# LAN9252-1.net
KiCad netlist of a schematic drawn in Altium Designer
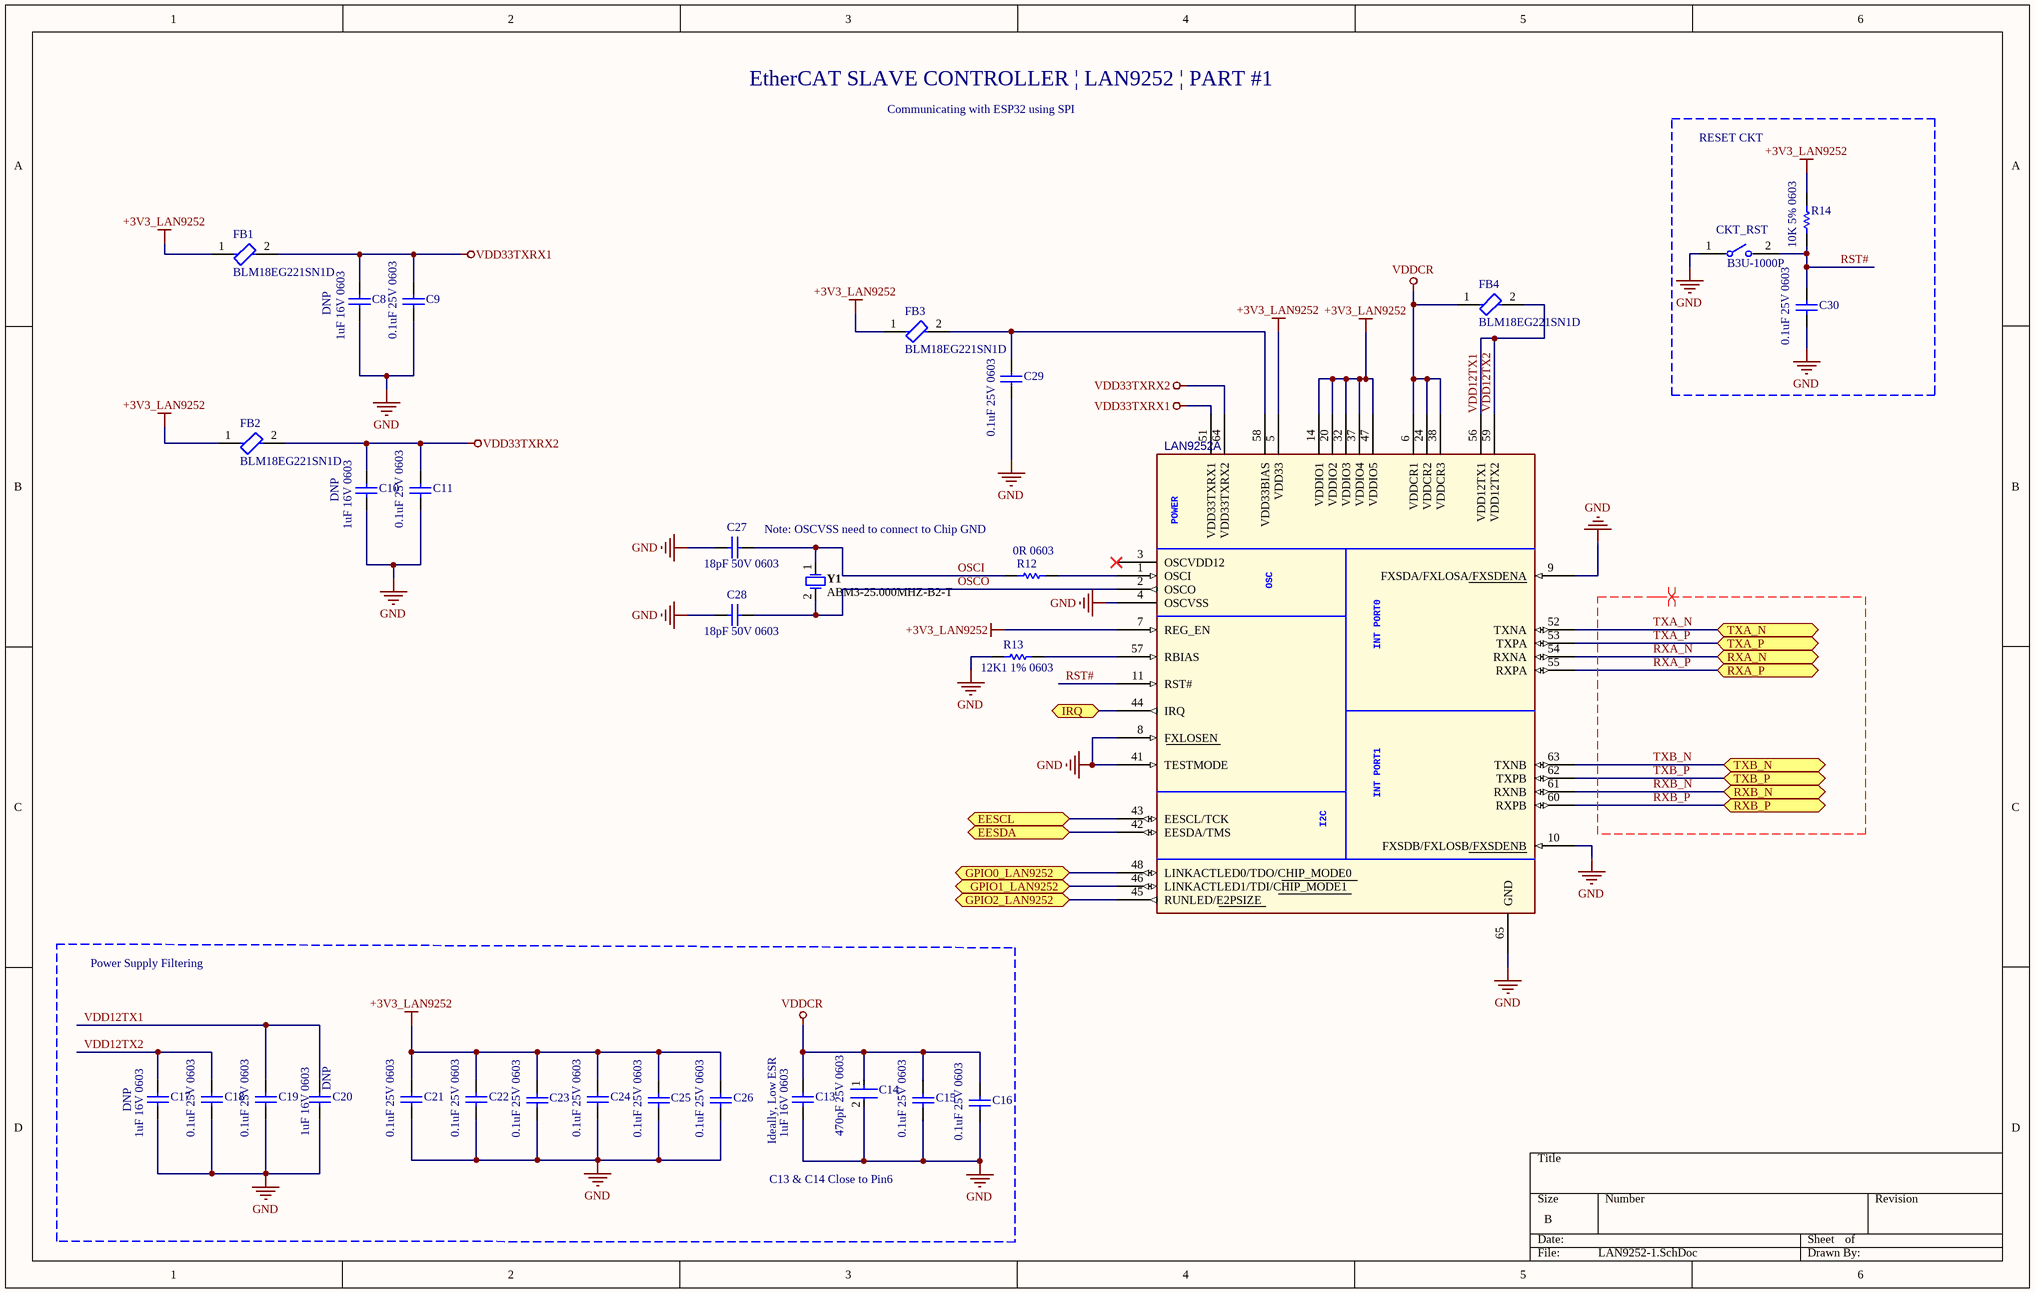
[diagram p0: LAN9252-1.SchDoc]

(export (version "E")
  (design (tool "Eeschema 10.0.6"))
  (components
    (comp (ref "C8")
      (value "1uF 16V 0603")
      (footprint "CAPC1608X90X35LL15T15")
      (fields (field (name "MANUFACTURER") "Kemet") (field (name "PART NUMBER") "C0603C105K4RACTU"))
      (libsource (lib "Altium Content Vault") (part "CAP"))
    )
    (comp (ref "C9")
      (value "0.1uF 25V 0603")
      (footprint "CAPC1608X90X35LL10T15")
      (fields (field (name "PART NUMBER") "GRM188R71E104KA01D") (field (name "MANUFACTURER") "Murata"))
      (libsource (lib "Altium Content Vault") (part "CAP"))
    )
    (comp (ref "C10")
      (value "1uF 16V 0603")
      (footprint "CAPC1608X90X35LL15T15")
      (fields (field (name "MANUFACTURER") "Kemet") (field (name "PART NUMBER") "C0603C105K4RACTU"))
      (libsource (lib "Altium Content Vault") (part "CAP"))
    )
    (comp (ref "C11")
      (value "0.1uF 25V 0603")
      (footprint "CAPC1608X90X35LL10T15")
      (fields (field (name "PART NUMBER") "GRM188R71E104KA01D") (field (name "MANUFACTURER") "Murata"))
      (libsource (lib "Altium Content Vault") (part "CAP"))
    )
    (comp (ref "C13")
      (value "1uF 16V 0603")
      (footprint "CAPC1608X90X35LL15T15")
      (fields (field (name "MANUFACTURER") "Kemet") (field (name "PART NUMBER") "C0603C105K4RACTU"))
      (libsource (lib "Altium Content Vault") (part "CAP"))
    )
    (comp (ref "C14")
      (value "470pF 25V 0603")
      (footprint "FP-C0603C-CF-MFG")
      (description "CAP CER 470PF 25V 10% X7R 0603")
      (fields (field (name "MANUFACTURER") "KEMET") (field (name "TOLERANCE") "0.1"))
      (libsource (lib "Altium Content Vault") (part "b4654b650e69147ec39a6b967a45e02"))
    )
    (comp (ref "C15")
      (value "0.1uF 25V 0603")
      (footprint "CAPC1608X90X35LL10T15")
      (fields (field (name "PART NUMBER") "GRM188R71E104KA01D") (field (name "MANUFACTURER") "Murata"))
      (libsource (lib "Altium Content Vault") (part "CAP"))
    )
    (comp (ref "C16")
      (value "0.1uF 25V 0603")
      (footprint "CAPC1608X90X35LL10T15")
      (fields (field (name "PART NUMBER") "GRM188R71E104KA01D") (field (name "MANUFACTURER") "Murata"))
      (libsource (lib "Altium Content Vault") (part "CAP"))
    )
    (comp (ref "C17")
      (value "1uF 16V 0603")
      (footprint "CAPC1608X90X35LL15T15")
      (fields (field (name "MANUFACTURER") "Kemet") (field (name "PART NUMBER") "C0603C105K4RACTU"))
      (libsource (lib "Altium Content Vault") (part "CAP"))
    )
    (comp (ref "C18")
      (value "0.1uF 25V 0603")
      (footprint "CAPC1608X90X35LL10T15")
      (fields (field (name "PART NUMBER") "GRM188R71E104KA01D") (field (name "MANUFACTURER") "Murata"))
      (libsource (lib "Altium Content Vault") (part "CAP"))
    )
    (comp (ref "C19")
      (value "0.1uF 25V 0603")
      (footprint "CAPC1608X90X35LL10T15")
      (fields (field (name "PART NUMBER") "GRM188R71E104KA01D") (field (name "MANUFACTURER") "Murata"))
      (libsource (lib "Altium Content Vault") (part "CAP"))
    )
    (comp (ref "C20")
      (value "1uF 16V 0603")
      (footprint "CAPC1608X90X35LL15T15")
      (fields (field (name "MANUFACTURER") "Kemet") (field (name "PART NUMBER") "C0603C105K4RACTU"))
      (libsource (lib "Altium Content Vault") (part "CAP"))
    )
    (comp (ref "C21")
      (value "0.1uF 25V 0603")
      (footprint "CAPC1608X90X35LL10T15")
      (fields (field (name "PART NUMBER") "GRM188R71E104KA01D") (field (name "MANUFACTURER") "Murata"))
      (libsource (lib "Altium Content Vault") (part "CAP"))
    )
    (comp (ref "C22")
      (value "0.1uF 25V 0603")
      (footprint "CAPC1608X90X35LL10T15")
      (fields (field (name "PART NUMBER") "GRM188R71E104KA01D") (field (name "MANUFACTURER") "Murata"))
      (libsource (lib "Altium Content Vault") (part "CAP"))
    )
    (comp (ref "C23")
      (value "0.1uF 25V 0603")
      (footprint "CAPC1608X90X35LL10T15")
      (fields (field (name "PART NUMBER") "GRM188R71E104KA01D") (field (name "MANUFACTURER") "Murata"))
      (libsource (lib "Altium Content Vault") (part "CAP"))
    )
    (comp (ref "C24")
      (value "0.1uF 25V 0603")
      (footprint "CAPC1608X90X35LL10T15")
      (fields (field (name "PART NUMBER") "GRM188R71E104KA01D") (field (name "MANUFACTURER") "Murata"))
      (libsource (lib "Altium Content Vault") (part "CAP"))
    )
    (comp (ref "C25")
      (value "0.1uF 25V 0603")
      (footprint "CAPC1608X90X35LL10T15")
      (fields (field (name "PART NUMBER") "GRM188R71E104KA01D") (field (name "MANUFACTURER") "Murata"))
      (libsource (lib "Altium Content Vault") (part "CAP"))
    )
    (comp (ref "C26")
      (value "0.1uF 25V 0603")
      (footprint "CAPC1608X90X35LL10T15")
      (fields (field (name "PART NUMBER") "GRM188R71E104KA01D") (field (name "MANUFACTURER") "Murata"))
      (libsource (lib "Altium Content Vault") (part "CAP"))
    )
    (comp (ref "C27")
      (value "18pF 50V 0603")
      (footprint "CAPC1608X90X40LL10T20")
      (description "Chip Capacitor, 18 pF, +/- 5%, 50 V, -55 to 125 degC, 0603 (1608 Metric), RoHS, Tape and Reel")
      (fields (field (name "TOLERANCE") "1%"))
      (libsource (lib "Altium Content Vault") (part "CAP-NP-2"))
    )
    (comp (ref "C28")
      (value "18pF 50V 0603")
      (footprint "CAPC1608X90X40LL10T20")
      (description "Chip Capacitor, 18 pF, +/- 5%, 50 V, -55 to 125 degC, 0603 (1608 Metric), RoHS, Tape and Reel")
      (fields (field (name "TOLERANCE") "1%"))
      (libsource (lib "Altium Content Vault") (part "CAP-NP-2"))
    )
    (comp (ref "C29")
      (value "0.1uF 25V 0603")
      (footprint "CAPC1608X90X35LL10T15")
      (fields (field (name "PART NUMBER") "GRM188R71E104KA01D") (field (name "MANUFACTURER") "Murata"))
      (libsource (lib "Altium Content Vault") (part "CAP"))
    )
    (comp (ref "C30")
      (value "0.1uF 25V 0603")
      (footprint "CAPC1608X90X35LL10T15")
      (fields (field (name "PART NUMBER") "GRM188R71E104KA01D") (field (name "MANUFACTURER") "Murata"))
      (libsource (lib "Altium Content Vault") (part "CAP"))
    )
    (comp (ref "CKT_RST")
      (value "B3U-1000P")
      (footprint "FP-B3U-1000P-MFG")
      (description "SWITCH TACTILE SPST-NO 0.05A 12V")
      (libsource (lib "Altium Content Vault") (part "ae622034201233ca1abcedc05908f33"))
    )
    (comp (ref "FB1")
      (value "BLM18EG221SN1D")
      (footprint "FP-BLM18-0_15-t0_8-MFG")
      (description "Chip Ferrite Bead, 0603, 220Ω @ 100MHz, 0.05Ω, 25%, 2A")
      (fields (field (name "TOLERANCE") "25%"))
      (libsource (lib "Altium Content Vault") (part "5f30dd21d616792df468990f7003faa"))
    )
    (comp (ref "FB2")
      (value "BLM18EG221SN1D")
      (footprint "FP-BLM18-0_15-t0_8-MFG")
      (description "Chip Ferrite Bead, 0603, 220Ω @ 100MHz, 0.05Ω, 25%, 2A")
      (fields (field (name "TOLERANCE") "25%"))
      (libsource (lib "Altium Content Vault") (part "5f30dd21d616792df468990f7003faa"))
    )
    (comp (ref "FB3")
      (value "BLM18EG221SN1D")
      (footprint "FP-BLM18-0_15-t0_8-MFG")
      (description "Chip Ferrite Bead, 0603, 220Ω @ 100MHz, 0.05Ω, 25%, 2A")
      (fields (field (name "TOLERANCE") "25%"))
      (libsource (lib "Altium Content Vault") (part "5f30dd21d616792df468990f7003faa"))
    )
    (comp (ref "FB4")
      (value "BLM18EG221SN1D")
      (footprint "FP-BLM18-0_15-t0_8-MFG")
      (description "Chip Ferrite Bead, 0603, 220Ω @ 100MHz, 0.05Ω, 25%, 2A")
      (fields (field (name "TOLERANCE") "25%"))
      (libsource (lib "Altium Content Vault") (part "5f30dd21d616792df468990f7003faa"))
    )
    (comp (ref "LAN9252")
      (value "~")
      (footprint "LAN9252_QFN")
      (description "IC, 2/3-Port EtherCAT® Slave Controller, QFN64")
      (fields (field (name "OWNER") "Manikandan"))
      (libsource (lib "UNG_UNG") (part "LAN9252_QFN64"))
    )
    (comp (ref "R12")
      (value "0R 0603")
      (footprint "RESC1608X55X25ML10T15")
      (description "Chip Resistor, 0 Ohm, +/- 5%, 0.1 W, -55 to 155 degC, 0603 (1608 Metric), RoHS, Tape and Reel")
      (fields (field (name "TOLERANCE") "5%") (field (name "MANUFACTURER") "Yageo"))
      (libsource (lib "Altium Content Vault") (part "RES-2"))
    )
    (comp (ref "R13")
      (value "12K1 1% 0603")
      (footprint "RESC0603X28X15ML05T05")
      (fields (field (name "PART NUMBER") "CRCW020112K1FNED") (field (name "MANUFACTURER") "Vishay Dale"))
      (libsource (lib "Altium Content Vault") (part "RES"))
    )
    (comp (ref "R14")
      (value "10K 5% 0603")
      (footprint "RESC1608X55X25ML10T15")
      (description "Chip Resistor, 10 KOhm, +/- 1%, 01 W, -55 to 155 degC, 0603 (1608 Metric), RoHS, Tape and Reel")
      (fields (field (name "MANUFACTURER") "Yageo") (field (name "TOLERANCE") "1%"))
      (libsource (lib "Altium Content Vault") (part "RES-2"))
    )
    (comp (ref "Y1")
      (value "ABM3-25.000MHZ-B2-T")
      (footprint "ABRA-ABM3_V")
      (description "Miniature Ceramic Crystal, 25 MHz, +/- 20 ppm, -20 to 70 degC, 2-Pin SMD, RoHS, Tape and Reel")
      (fields (field (name "TOLERANCE") "20PPM") (field (name "MANUFACTURER") "ABRACON"))
      (libsource (lib "Altium Content Vault") (part "XTAL-1-2-2"))
    )
  )
  (nets
    (net (code "1") (name "+3V3_LAN9252") (class "Default")
      (node (ref "C21") (pin "2") (pinfunction "2_2") (pintype "passive"))
      (node (ref "C22") (pin "2") (pinfunction "2_2") (pintype "passive"))
      (node (ref "C23") (pin "2") (pinfunction "2_2") (pintype "passive"))
      (node (ref "C24") (pin "2") (pinfunction "2_2") (pintype "passive"))
      (node (ref "C25") (pin "2") (pinfunction "2_2") (pintype "passive"))
      (node (ref "C26") (pin "2") (pinfunction "2_2") (pintype "passive"))
      (node (ref "FB1") (pin "1") (pinfunction "1_1") (pintype "passive"))
      (node (ref "FB2") (pin "1") (pinfunction "1_1") (pintype "passive"))
      (node (ref "FB3") (pin "1") (pinfunction "1_1") (pintype "passive"))
      (node (ref "LAN9252") (pin "14") (pinfunction "VDDIO1_14") (pintype "power_in"))
      (node (ref "LAN9252") (pin "20") (pinfunction "VDDIO2_20") (pintype "power_in"))
      (node (ref "LAN9252") (pin "32") (pinfunction "VDDIO3_32") (pintype "power_in"))
      (node (ref "LAN9252") (pin "37") (pinfunction "VDDIO4_37") (pintype "power_in"))
      (node (ref "LAN9252") (pin "47") (pinfunction "VDDIO5_47") (pintype "power_in"))
      (node (ref "LAN9252") (pin "5") (pinfunction "VDD33_5") (pintype "power_in"))
      (node (ref "LAN9252") (pin "7") (pinfunction "REG_EN_7") (pintype "input"))
      (node (ref "R14") (pin "2") (pinfunction "2_2") (pintype "passive"))
    )
    (net (code "2") (name "/EESCL") (class "Default")
      (node (ref "LAN9252") (pin "43") (pinfunction "EESCL/TCK_43") (pintype "bidirectional"))
    )
    (net (code "3") (name "/EESDA") (class "Default")
      (node (ref "LAN9252") (pin "42") (pinfunction "EESDA/TMS_42") (pintype "bidirectional"))
    )
    (net (code "4") (name "/GPIO0_LAN9252") (class "Default")
      (node (ref "LAN9252") (pin "48") (pinfunction "LINKACTLED0/TDO/CHIP_MODE0_48") (pintype "bidirectional"))
    )
    (net (code "5") (name "/GPIO1_LAN9252") (class "Default")
      (node (ref "LAN9252") (pin "46") (pinfunction "LINKACTLED1/TDI/CHIP_MODE1_46") (pintype "bidirectional"))
    )
    (net (code "6") (name "/GPIO2_LAN9252") (class "Default")
      (node (ref "LAN9252") (pin "45") (pinfunction "RUNLED/E2PSIZE_45") (pintype "output"))
    )
    (net (code "7") (name "/IRQ") (class "Default")
      (node (ref "LAN9252") (pin "44") (pinfunction "IRQ_44") (pintype "output"))
    )
    (net (code "8") (name "/OSCI") (class "Default")
      (node (ref "C27") (pin "2") (pinfunction "2_2") (pintype "passive"))
      (node (ref "R12") (pin "1") (pinfunction "1_1") (pintype "passive"))
      (node (ref "Y1") (pin "1") (pinfunction "1_1") (pintype "passive"))
    )
    (net (code "9") (name "/OSCO") (class "Default")
      (node (ref "C28") (pin "2") (pinfunction "2_2") (pintype "passive"))
      (node (ref "LAN9252") (pin "2") (pinfunction "OSCO_2") (pintype "output"))
      (node (ref "Y1") (pin "2") (pinfunction "2_2") (pintype "passive"))
    )
    (net (code "10") (name "/RST#") (class "Default")
      (node (ref "C30") (pin "2") (pinfunction "2_2") (pintype "passive"))
      (node (ref "CKT_RST") (pin "2") (pinfunction "2_2") (pintype "passive"))
      (node (ref "LAN9252") (pin "11") (pinfunction "RST#_11") (pintype "input"))
      (node (ref "R14") (pin "1") (pinfunction "1_1") (pintype "passive"))
    )
    (net (code "11") (name "/RXA_N") (class "Default")
      (node (ref "LAN9252") (pin "54") (pinfunction "RXNA_54") (pintype "bidirectional"))
    )
    (net (code "12") (name "/RXA_P") (class "Default")
      (node (ref "LAN9252") (pin "55") (pinfunction "RXPA_55") (pintype "bidirectional"))
    )
    (net (code "13") (name "/RXB_N") (class "Default")
      (node (ref "LAN9252") (pin "61") (pinfunction "RXNB_61") (pintype "bidirectional"))
    )
    (net (code "14") (name "/RXB_P") (class "Default")
      (node (ref "LAN9252") (pin "60") (pinfunction "RXPB_60") (pintype "bidirectional"))
    )
    (net (code "15") (name "/TXA_N") (class "Default")
      (node (ref "LAN9252") (pin "52") (pinfunction "TXNA_52") (pintype "bidirectional"))
    )
    (net (code "16") (name "/TXA_P") (class "Default")
      (node (ref "LAN9252") (pin "53") (pinfunction "TXPA_53") (pintype "bidirectional"))
    )
    (net (code "17") (name "/TXB_N") (class "Default")
      (node (ref "LAN9252") (pin "63") (pinfunction "TXNB_63") (pintype "bidirectional"))
    )
    (net (code "18") (name "/TXB_P") (class "Default")
      (node (ref "LAN9252") (pin "62") (pinfunction "TXPB_62") (pintype "bidirectional"))
    )
    (net (code "19") (name "/VDD12TX1") (class "Default")
      (node (ref "C17") (pin "2") (pinfunction "2_2") (pintype "passive"))
      (node (ref "C18") (pin "2") (pinfunction "2_2") (pintype "passive"))
      (node (ref "C19") (pin "2") (pinfunction "2_2") (pintype "passive"))
      (node (ref "C20") (pin "2") (pinfunction "2_2") (pintype "passive"))
      (node (ref "FB4") (pin "2") (pinfunction "2_2") (pintype "passive"))
      (node (ref "LAN9252") (pin "56") (pinfunction "VDD12TX1_56") (pintype "power_in"))
      (node (ref "LAN9252") (pin "59") (pinfunction "VDD12TX2_59") (pintype "power_in"))
    )
    (net (code "20") (name "GND") (class "Default")
      (node (ref "C10") (pin "1") (pinfunction "1_1") (pintype "passive"))
      (node (ref "C11") (pin "1") (pinfunction "1_1") (pintype "passive"))
      (node (ref "C13") (pin "1") (pinfunction "1_1") (pintype "passive"))
      (node (ref "C14") (pin "2") (pinfunction "2_2") (pintype "passive"))
      (node (ref "C15") (pin "1") (pinfunction "1_1") (pintype "passive"))
      (node (ref "C16") (pin "1") (pinfunction "1_1") (pintype "passive"))
      (node (ref "C17") (pin "1") (pinfunction "1_1") (pintype "passive"))
      (node (ref "C18") (pin "1") (pinfunction "1_1") (pintype "passive"))
      (node (ref "C19") (pin "1") (pinfunction "1_1") (pintype "passive"))
      (node (ref "C20") (pin "1") (pinfunction "1_1") (pintype "passive"))
      (node (ref "C21") (pin "1") (pinfunction "1_1") (pintype "passive"))
      (node (ref "C22") (pin "1") (pinfunction "1_1") (pintype "passive"))
      (node (ref "C23") (pin "1") (pinfunction "1_1") (pintype "passive"))
      (node (ref "C24") (pin "1") (pinfunction "1_1") (pintype "passive"))
      (node (ref "C25") (pin "1") (pinfunction "1_1") (pintype "passive"))
      (node (ref "C26") (pin "1") (pinfunction "1_1") (pintype "passive"))
      (node (ref "C27") (pin "1") (pinfunction "1_1") (pintype "passive"))
      (node (ref "C28") (pin "1") (pinfunction "1_1") (pintype "passive"))
      (node (ref "C29") (pin "1") (pinfunction "1_1") (pintype "passive"))
      (node (ref "C30") (pin "1") (pinfunction "1_1") (pintype "passive"))
      (node (ref "C8") (pin "1") (pinfunction "1_1") (pintype "passive"))
      (node (ref "C9") (pin "1") (pinfunction "1_1") (pintype "passive"))
      (node (ref "CKT_RST") (pin "1") (pinfunction "1_1") (pintype "passive"))
      (node (ref "LAN9252") (pin "10") (pinfunction "FXSDB/FXLOSB/FXSDENB_10") (pintype "input"))
      (node (ref "LAN9252") (pin "4") (pinfunction "OSCVSS_4") (pintype "power_in"))
      (node (ref "LAN9252") (pin "41") (pinfunction "TESTMODE_41") (pintype "input"))
      (node (ref "LAN9252") (pin "65") (pinfunction "GND_65") (pintype "power_in"))
      (node (ref "LAN9252") (pin "8") (pinfunction "FXLOSEN_8") (pintype "input"))
      (node (ref "LAN9252") (pin "9") (pinfunction "FXSDA/FXLOSA/FXSDENA_9") (pintype "input"))
      (node (ref "R13") (pin "1") (pinfunction "1_1") (pintype "passive"))
    )
    (net (code "21") (name "Net-(LAN9252A-OSCI)") (class "Default")
      (node (ref "LAN9252") (pin "1") (pinfunction "OSCI_1") (pintype "input"))
      (node (ref "R12") (pin "2") (pinfunction "2_2") (pintype "passive"))
    )
    (net (code "22") (name "Net-(LAN9252A-RBIAS)") (class "Default")
      (node (ref "LAN9252") (pin "57") (pinfunction "RBIAS_57") (pintype "input"))
      (node (ref "R13") (pin "2") (pinfunction "2_2") (pintype "passive"))
    )
    (net (code "23") (name "Net-(LAN9252A-VDD33BIAS)") (class "Default")
      (node (ref "C29") (pin "2") (pinfunction "2_2") (pintype "passive"))
      (node (ref "FB3") (pin "2") (pinfunction "2_2") (pintype "passive"))
      (node (ref "LAN9252") (pin "58") (pinfunction "VDD33BIAS_58") (pintype "power_in"))
    )
    (net (code "24") (name "VDD33TXRX1") (class "Default")
      (node (ref "C8") (pin "2") (pinfunction "2_2") (pintype "passive"))
      (node (ref "C9") (pin "2") (pinfunction "2_2") (pintype "passive"))
      (node (ref "FB1") (pin "2") (pinfunction "2_2") (pintype "passive"))
      (node (ref "LAN9252") (pin "51") (pinfunction "VDD33TXRX1_51") (pintype "power_in"))
    )
    (net (code "25") (name "VDD33TXRX2") (class "Default")
      (node (ref "C10") (pin "2") (pinfunction "2_2") (pintype "passive"))
      (node (ref "C11") (pin "2") (pinfunction "2_2") (pintype "passive"))
      (node (ref "FB2") (pin "2") (pinfunction "2_2") (pintype "passive"))
      (node (ref "LAN9252") (pin "64") (pinfunction "VDD33TXRX2_64") (pintype "power_in"))
    )
    (net (code "26") (name "VDDCR") (class "Default")
      (node (ref "C13") (pin "2") (pinfunction "2_2") (pintype "passive"))
      (node (ref "C14") (pin "1") (pinfunction "1_1") (pintype "passive"))
      (node (ref "C15") (pin "2") (pinfunction "2_2") (pintype "passive"))
      (node (ref "C16") (pin "2") (pinfunction "2_2") (pintype "passive"))
      (node (ref "FB4") (pin "1") (pinfunction "1_1") (pintype "passive"))
      (node (ref "LAN9252") (pin "24") (pinfunction "VDDCR2_24") (pintype "power_in"))
      (node (ref "LAN9252") (pin "38") (pinfunction "VDDCR3_38") (pintype "power_in"))
      (node (ref "LAN9252") (pin "6") (pinfunction "VDDCR1_6") (pintype "power_in"))
    )
    (net (code "27") (name "unconnected-(LAN9252A-OSCVDD12-Pad3)") (class "Default")
      (node (ref "LAN9252") (pin "3") (pinfunction "OSCVDD12_3") (pintype "power_in+no_connect"))
    )
  )
)
